# Board_MIL_AND_RIGHT_PROTO_V2_Mob_Project.net
KiCad netlist of a schematic drawn in EAGLE
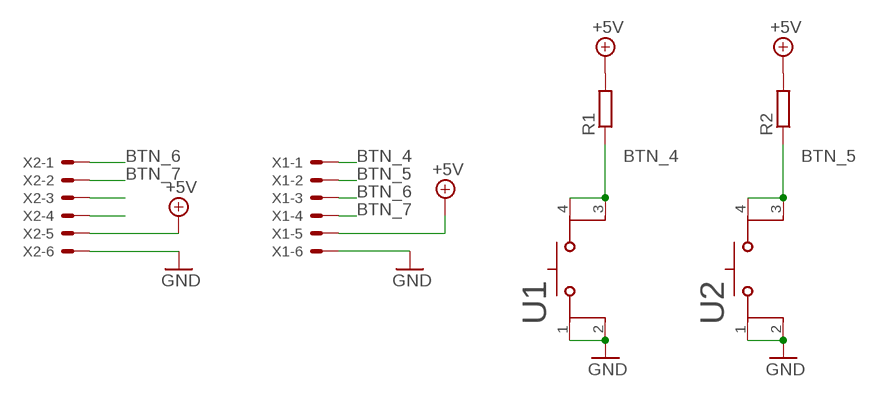
[diagram p0: schematic, sheet 1]

(export (version "E")
  (design (tool "Eeschema 10.0.6"))
  (components
    (comp (ref "R1")
      (value "R-EU_M0805")
      (footprint "eagle-import:M0805")
      (libsource (lib "eagle-import") (part "R-EU_M0805"))
    )
    (comp (ref "R2")
      (value "R-EU_M0805")
      (footprint "eagle-import:M0805")
      (libsource (lib "eagle-import") (part "R-EU_M0805"))
    )
    (comp (ref "U1")
      (value "4-1437565-1")
      (footprint "eagle-import:SW4_236X236H5MM")
      (fields (field (name "COPYRIGHT") "Copyright (C) 2016 Accelerated Designs. All rights reserved"))
      (libsource (lib "eagle-import") (part "4-1437565-1"))
    )
    (comp (ref "U2")
      (value "4-1437565-1")
      (footprint "eagle-import:SW4_236X236H5MM")
      (fields (field (name "COPYRIGHT") "Copyright (C) 2016 Accelerated Designs. All rights reserved"))
      (libsource (lib "eagle-import") (part "4-1437565-1"))
    )
    (comp (ref "X1")
      (value "C-GRID-06-70543")
      (footprint "eagle-import:70543-06")
      (fields (field (name "MF") "MOLEX"))
      (libsource (lib "eagle-import") (part "C-GRID-06-70543"))
    )
    (comp (ref "X2")
      (value "C-GRID-06-70543")
      (footprint "eagle-import:70543-06")
      (fields (field (name "MF") "MOLEX"))
      (libsource (lib "eagle-import") (part "C-GRID-06-70543"))
    )
  )
  (nets
    (net (code "1") (name "+5V") (class "Default")
      (node (ref "R1") (pin "2") (pinfunction "2_2") (pintype "passive"))
      (node (ref "R2") (pin "2") (pinfunction "2_2") (pintype "passive"))
      (node (ref "X1") (pin "5") (pinfunction "S_5") (pintype "passive"))
      (node (ref "X2") (pin "5") (pinfunction "S_5") (pintype "passive"))
    )
    (net (code "2") (name "/BTN_4") (class "Default")
      (node (ref "R1") (pin "1") (pinfunction "1_1") (pintype "passive"))
      (node (ref "U1") (pin "3") (pinfunction "3_3") (pintype "passive"))
      (node (ref "U1") (pin "4") (pinfunction "4_4") (pintype "passive"))
      (node (ref "X1") (pin "1") (pinfunction "S_1") (pintype "passive"))
    )
    (net (code "3") (name "/BTN_5") (class "Default")
      (node (ref "R2") (pin "1") (pinfunction "1_1") (pintype "passive"))
      (node (ref "U2") (pin "3") (pinfunction "3_3") (pintype "passive"))
      (node (ref "U2") (pin "4") (pinfunction "4_4") (pintype "passive"))
      (node (ref "X1") (pin "2") (pinfunction "S_2") (pintype "passive"))
    )
    (net (code "4") (name "/BTN_6") (class "Default")
      (node (ref "X1") (pin "3") (pinfunction "S_3") (pintype "passive"))
      (node (ref "X2") (pin "1") (pinfunction "S_1") (pintype "passive"))
    )
    (net (code "5") (name "/BTN_7") (class "Default")
      (node (ref "X1") (pin "4") (pinfunction "S_4") (pintype "passive"))
      (node (ref "X2") (pin "2") (pinfunction "S_2") (pintype "passive"))
    )
    (net (code "6") (name "GND") (class "Default")
      (node (ref "U1") (pin "1") (pinfunction "1_1") (pintype "passive"))
      (node (ref "U1") (pin "2") (pinfunction "2_2") (pintype "passive"))
      (node (ref "U2") (pin "1") (pinfunction "1_1") (pintype "passive"))
      (node (ref "U2") (pin "2") (pinfunction "2_2") (pintype "passive"))
      (node (ref "X1") (pin "6") (pinfunction "S_6") (pintype "passive"))
      (node (ref "X2") (pin "6") (pinfunction "S_6") (pintype "passive"))
    )
    (net (code "7") (name "unconnected-(X2C-S-Pad3)") (class "Default")
      (node (ref "X2") (pin "3") (pinfunction "S_3") (pintype "passive"))
    )
    (net (code "8") (name "unconnected-(X2D-S-Pad4)") (class "Default")
      (node (ref "X2") (pin "4") (pinfunction "S_4") (pintype "passive"))
    )
  )
)
